# BoostUC3843.net
KiCad netlist of a schematic drawn in Altium Designer
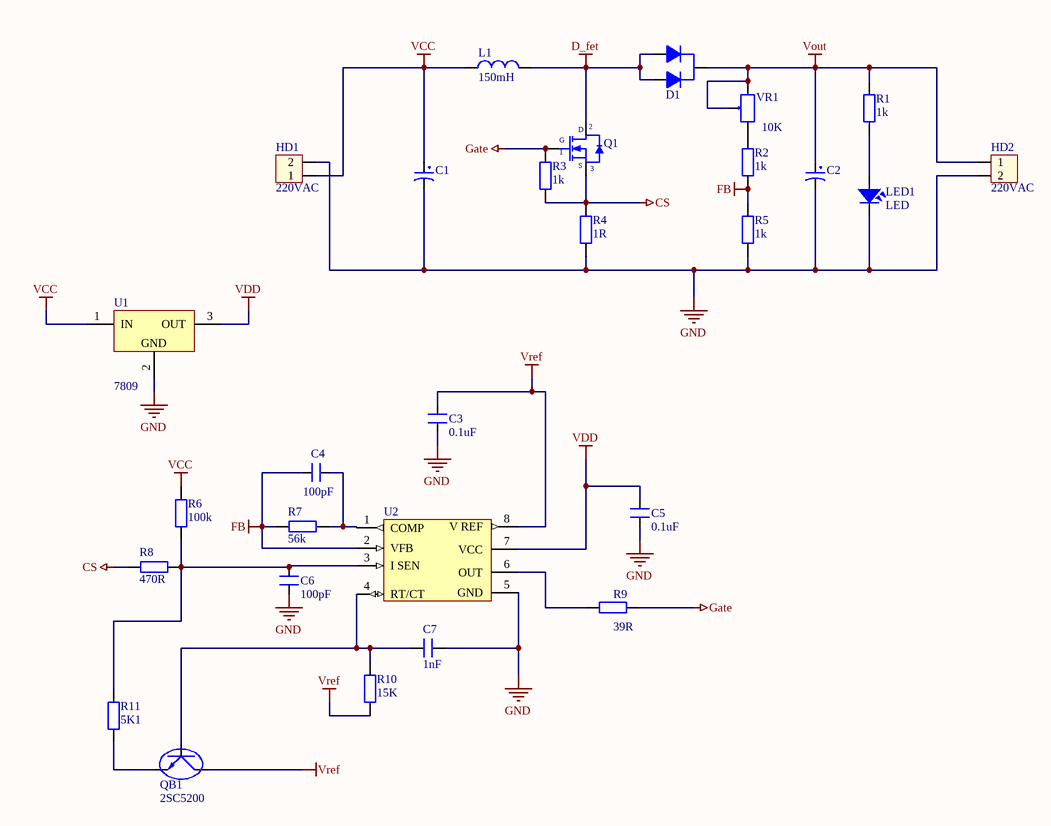
[diagram p0: BoostUC3843.SchDoc]

(export (version "E")
  (design (tool "Eeschema 10.0.6"))
  (components
    (comp (ref "C1")
      (value "100uF/35V")
      (footprint "CP1.5/3.4")
      (description "Cap 100uF/35V - 470uF/16V")
      (libsource (lib "PELAB") (part "CP3"))
    )
    (comp (ref "C2")
      (value "100uF/35V")
      (footprint "CA-ALU-10GR")
      (description "Cap 100uF/35V - 470uF/16V")
      (libsource (lib "PELAB") (part "CP3"))
    )
    (comp (ref "C3")
      (value "0.1uF")
      (footprint "CN-SMD-0805")
      (description "Cap SMD")
      (libsource (lib "Flyback") (part "CM"))
    )
    (comp (ref "C4")
      (value "100pF")
      (footprint "CN-SMD-0805")
      (description "Cap SMD")
      (libsource (lib "Flyback") (part "CM"))
    )
    (comp (ref "C5")
      (value "0.1uF")
      (footprint "CN-SMD-0805")
      (description "Cap SMD")
      (libsource (lib "Flyback") (part "CM"))
    )
    (comp (ref "C6")
      (value "100pF")
      (footprint "CN-SMD-0805")
      (description "Cap SMD")
      (libsource (lib "Flyback") (part "CM"))
    )
    (comp (ref "C7")
      (value "1nF")
      (footprint "CN-SMD-0805")
      (description "Cap SMD")
      (libsource (lib "PELAB") (part "CM"))
    )
    (comp (ref "D1") (value "Diode") (footprint "TO-220") (libsource (lib "Flyback") (part "Diode")))
    (comp (ref "HD1")
      (value "220VAC")
      (footprint "HED2")
      (description "Header 2 (Green)")
      (libsource (lib "") (part "Hed2_1"))
    )
    (comp (ref "HD2")
      (value "220VAC")
      (footprint "HED2")
      (description "Header 2 (Green)")
      (libsource (lib "PELAB") (part "Hed2"))
    )
    (comp (ref "L1")
      (value "150mH")
      (footprint "0077930A7-core")
      (description "Inductor")
      (libsource (lib "PELAB") (part "L1"))
    )
    (comp (ref "LED1")
      (value "LED")
      (footprint "LED-3")
      (description "LED Single colour Green and Red")
      (libsource (lib "My Library") (part "LED"))
    )
    (comp (ref "Q1")
      (value "IRF840")
      (footprint "TO-220")
      (description "MOSFET N - CHANNEL 500V - 0.75 - 8A - TO-220")
      (libsource (lib "Flyback") (part "IRF840"))
    )
    (comp (ref "QB1")
      (value "2SC5200")
      (footprint "SOT23")
      (description "Transistor Power Supply")
      (libsource (lib "My Library") (part "2SC5200"))
    )
    (comp (ref "R1")
      (value "1k")
      (footprint "RES-SMD-0805")
      (description "Resistor 1/4W")
      (libsource (lib "PELAB") (part "RES_SMD"))
    )
    (comp (ref "R2")
      (value "1k")
      (footprint "RES-SMD-0805")
      (description "Resistor 1/4W")
      (libsource (lib "PELAB") (part "RES_SMD"))
    )
    (comp (ref "R3")
      (value "1k")
      (footprint "RES-SMD-0805")
      (description "Resistor 1/4W")
      (libsource (lib "PELAB") (part "RES_SMD"))
    )
    (comp (ref "R4")
      (value "1R")
      (footprint "RES-SMD-2512")
      (description "Resistor 1/4W")
      (libsource (lib "PELAB") (part "RES_SMD"))
    )
    (comp (ref "R5")
      (value "1k")
      (footprint "RES-SMD-0805")
      (description "Resistor 1/4W")
      (libsource (lib "PELAB") (part "RES_SMD"))
    )
    (comp (ref "R6")
      (value "100k")
      (footprint "RES-SMD-0805")
      (description "Resistor 1/4W")
      (libsource (lib "PELAB") (part "RES_SMD"))
    )
    (comp (ref "R7")
      (value "56k")
      (footprint "RES-SMD-0805")
      (description "Resistor 1/4W")
      (libsource (lib "PELAB") (part "RES_SMD"))
    )
    (comp (ref "R8")
      (value "470R")
      (footprint "RES-SMD-0805")
      (description "Resistor 1/4W")
      (libsource (lib "PELAB") (part "RES_SMD"))
    )
    (comp (ref "R9")
      (value "39R")
      (footprint "R1206")
      (description "Resistor 1/4W")
      (libsource (lib "PELAB") (part "RES_SMD"))
    )
    (comp (ref "R10")
      (value "15K")
      (footprint "RES-SMD-0805")
      (description "Resistor 1/4W")
      (libsource (lib "PELAB") (part "RES_SMD"))
    )
    (comp (ref "R11")
      (value "5K1")
      (footprint "RES-SMD-0805")
      (description "Resistor 1/4W")
      (libsource (lib "PELAB") (part "RES_SMD"))
    )
    (comp (ref "U1")
      (value "7809")
      (footprint "TO-252")
      (description "Positive Voltage Regulator")
      (fields (field (name "PUBLISHER") "Altium Limited"))
      (libsource (lib "My Library") (part "7809"))
    )
    (comp (ref "U2")
      (value "UC3843AN")
      (footprint "SO-8")
      (description "High-Performance Current Mode PWM Controller")
      (fields (field (name "PUBLISHER") "Altium Limited"))
      (libsource (lib "My Library") (part "UC3843AN"))
    )
    (comp (ref "VR1")
      (value "10K")
      (footprint "VR1")
      (description "Var Resistor")
      (libsource (lib "PELAB") (part "VR"))
    )
  )
  (nets
    (net (code "1") (name "CS") (class "Default")
      (node (ref "Q1") (pin "3") (pinfunction "S_3") (pintype "passive"))
      (node (ref "R3") (pin "1") (pinfunction "1_1") (pintype "passive"))
      (node (ref "R4") (pin "2") (pinfunction "2_2") (pintype "passive"))
      (node (ref "R8") (pin "2") (pinfunction "2_2") (pintype "passive"))
    )
    (net (code "2") (name "D_fet") (class "Default")
      (node (ref "D1") (pin "1") (pinfunction "A_1") (pintype "passive"))
      (node (ref "D1") (pin "3") (pinfunction "A_3") (pintype "passive"))
      (node (ref "L1") (pin "2") (pinfunction "2_2") (pintype "passive"))
      (node (ref "Q1") (pin "2") (pinfunction "D_2") (pintype "passive"))
    )
    (net (code "3") (name "FB") (class "Default")
      (node (ref "C4") (pin "2") (pinfunction "2_2") (pintype "passive"))
      (node (ref "R2") (pin "1") (pinfunction "1_1") (pintype "passive"))
      (node (ref "R5") (pin "2") (pinfunction "2_2") (pintype "passive"))
      (node (ref "R7") (pin "2") (pinfunction "2_2") (pintype "passive"))
      (node (ref "U2") (pin "2") (pinfunction "VFB_2") (pintype "input"))
    )
    (net (code "4") (name "GND") (class "Default")
      (node (ref "C1") (pin "2") (pinfunction "2_2") (pintype "passive"))
      (node (ref "C2") (pin "2") (pinfunction "2_2") (pintype "passive"))
      (node (ref "C3") (pin "1") (pinfunction "1_1") (pintype "passive"))
      (node (ref "C5") (pin "1") (pinfunction "1_1") (pintype "passive"))
      (node (ref "C6") (pin "1") (pinfunction "1_1") (pintype "passive"))
      (node (ref "C7") (pin "1") (pinfunction "1_1") (pintype "passive"))
      (node (ref "HD1") (pin "2") (pinfunction "2_2") (pintype "passive"))
      (node (ref "HD2") (pin "2") (pinfunction "2_2") (pintype "passive"))
      (node (ref "LED1") (pin "2") (pinfunction "2_2") (pintype "passive"))
      (node (ref "R4") (pin "1") (pinfunction "1_1") (pintype "passive"))
      (node (ref "R5") (pin "1") (pinfunction "1_1") (pintype "passive"))
      (node (ref "U1") (pin "2") (pinfunction "GND_2") (pintype "power_in"))
      (node (ref "U2") (pin "5") (pinfunction "GND_5") (pintype "power_in"))
    )
    (net (code "5") (name "Gate") (class "Default")
      (node (ref "Q1") (pin "1") (pinfunction "G_1") (pintype "passive"))
      (node (ref "R3") (pin "2") (pinfunction "2_2") (pintype "passive"))
      (node (ref "R9") (pin "2") (pinfunction "2_2") (pintype "passive"))
    )
    (net (code "6") (name "Net-(LED1-Pad1)") (class "Default")
      (node (ref "LED1") (pin "1") (pinfunction "1_1") (pintype "passive"))
      (node (ref "R1") (pin "1") (pinfunction "1_1") (pintype "passive"))
    )
    (net (code "7") (name "Net-(QB1-B)") (class "Default")
      (node (ref "C7") (pin "2") (pinfunction "2_2") (pintype "passive"))
      (node (ref "QB1") (pin "1") (pinfunction "B_1") (pintype "passive"))
      (node (ref "R10") (pin "2") (pinfunction "2_2") (pintype "passive"))
      (node (ref "U2") (pin "4") (pinfunction "RT/CT_4") (pintype "bidirectional"))
    )
    (net (code "8") (name "Net-(QB1-E)") (class "Default")
      (node (ref "QB1") (pin "3") (pinfunction "E_3") (pintype "passive"))
      (node (ref "R11") (pin "1") (pinfunction "1_1") (pintype "passive"))
    )
    (net (code "9") (name "Net-(R2-Pad2)") (class "Default")
      (node (ref "R2") (pin "2") (pinfunction "2_2") (pintype "passive"))
      (node (ref "VR1") (pin "1") (pinfunction "1_1") (pintype "passive"))
    )
    (net (code "10") (name "Net-(U2-COMP)") (class "Default")
      (node (ref "C4") (pin "1") (pinfunction "1_1") (pintype "passive"))
      (node (ref "R7") (pin "1") (pinfunction "1_1") (pintype "passive"))
      (node (ref "U2") (pin "1") (pinfunction "COMP_1") (pintype "output"))
    )
    (net (code "11") (name "Net-(U2-I_SEN)") (class "Default")
      (node (ref "C6") (pin "2") (pinfunction "2_2") (pintype "passive"))
      (node (ref "R11") (pin "2") (pinfunction "2_2") (pintype "passive"))
      (node (ref "R6") (pin "2") (pinfunction "2_2") (pintype "passive"))
      (node (ref "R8") (pin "1") (pinfunction "1_1") (pintype "passive"))
      (node (ref "U2") (pin "3") (pinfunction "I_SEN_3") (pintype "input"))
    )
    (net (code "12") (name "Net-(U2-OUT)") (class "Default")
      (node (ref "R9") (pin "1") (pinfunction "1_1") (pintype "passive"))
      (node (ref "U2") (pin "6") (pinfunction "OUT_6") (pintype "tri_state"))
    )
    (net (code "13") (name "VCC") (class "Default")
      (node (ref "C1") (pin "1") (pinfunction "1_1") (pintype "passive"))
      (node (ref "HD1") (pin "1") (pinfunction "1_1") (pintype "passive"))
      (node (ref "L1") (pin "1") (pinfunction "1_1") (pintype "passive"))
      (node (ref "R6") (pin "1") (pinfunction "1_1") (pintype "passive"))
      (node (ref "U1") (pin "1") (pinfunction "IN_1") (pintype "power_in"))
    )
    (net (code "14") (name "VDD") (class "Default")
      (node (ref "C5") (pin "2") (pinfunction "2_2") (pintype "passive"))
      (node (ref "U1") (pin "3") (pinfunction "OUT_3") (pintype "power_in"))
      (node (ref "U2") (pin "7") (pinfunction "VCC_7") (pintype "power_in"))
    )
    (net (code "15") (name "Vout") (class "Default")
      (node (ref "C2") (pin "1") (pinfunction "1_1") (pintype "passive"))
      (node (ref "D1") (pin "2") (pinfunction "K_2") (pintype "passive"))
      (node (ref "HD2") (pin "1") (pinfunction "1_1") (pintype "passive"))
      (node (ref "R1") (pin "2") (pinfunction "2_2") (pintype "passive"))
      (node (ref "VR1") (pin "2") (pinfunction "2_2") (pintype "passive"))
      (node (ref "VR1") (pin "3") (pinfunction "3_3") (pintype "passive"))
    )
    (net (code "16") (name "Vref") (class "Default")
      (node (ref "C3") (pin "2") (pinfunction "2_2") (pintype "passive"))
      (node (ref "QB1") (pin "2") (pinfunction "C_2") (pintype "passive"))
      (node (ref "R10") (pin "1") (pinfunction "1_1") (pintype "passive"))
      (node (ref "U2") (pin "8") (pinfunction "V_REF_8") (pintype "output"))
    )
  )
)
